# bike_light.net
KiCad netlist of a schematic drawn in EAGLE
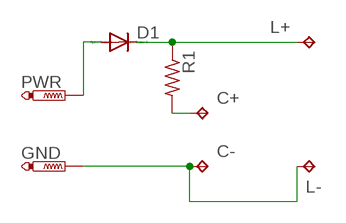
[diagram p0: schematic, sheet 1]

(export (version "E")
  (design (tool "Eeschema 10.0.6"))
  (components
    (comp (ref "C+")
      (value "TPTP20SQ")
      (footprint "eagle-import:TP20SQ")
      (libsource (lib "eagle-import") (part "TPTP20SQ"))
    )
    (comp (ref "C-")
      (value "TPTP20SQ")
      (footprint "eagle-import:TP20SQ")
      (libsource (lib "eagle-import") (part "TPTP20SQ"))
    )
    (comp (ref "D1")
      (value "DIODE-DO-214AC")
      (footprint "eagle-import:DO-214AC")
      (libsource (lib "eagle-import") (part "DIODE-DO-214AC"))
    )
    (comp (ref "GND")
      (value "PTR1PAD1-13Y")
      (footprint "eagle-import:P1-13Y")
      (libsource (lib "eagle-import") (part "PTR1PAD1-13Y"))
    )
    (comp (ref "L+")
      (value "TPTP20SQ")
      (footprint "eagle-import:TP20SQ")
      (libsource (lib "eagle-import") (part "TPTP20SQ"))
    )
    (comp (ref "L-")
      (value "TPTP20SQ")
      (footprint "eagle-import:TP20SQ")
      (libsource (lib "eagle-import") (part "TPTP20SQ"))
    )
    (comp (ref "PWR")
      (value "PTR1PAD1-13Y")
      (footprint "eagle-import:P1-13Y")
      (libsource (lib "eagle-import") (part "PTR1PAD1-13Y"))
    )
    (comp (ref "R1")
      (value "R-US_M1206")
      (footprint "eagle-import:M1206")
      (libsource (lib "eagle-import") (part "R-US_M1206"))
    )
  )
  (nets
    (net (code "1") (name "Net-(C+-PadTP)") (class "Default")
      (node (ref "C+") (pin "TP") (pinfunction "TP_TP") (pintype "input"))
      (node (ref "R1") (pin "2") (pinfunction "2_2") (pintype "passive"))
    )
    (net (code "2") (name "Net-(C--PadTP)") (class "Default")
      (node (ref "C-") (pin "TP") (pinfunction "TP_TP") (pintype "input"))
      (node (ref "GND") (pin "TP") (pinfunction "TP_TP") (pintype "input"))
      (node (ref "L-") (pin "TP") (pinfunction "TP_TP") (pintype "input"))
    )
    (net (code "3") (name "Net-(D1-PadA)") (class "Default")
      (node (ref "D1") (pin "A") (pinfunction "A_A") (pintype "passive"))
      (node (ref "PWR") (pin "TP") (pinfunction "TP_TP") (pintype "input"))
    )
    (net (code "4") (name "Net-(D1-PadC)") (class "Default")
      (node (ref "D1") (pin "C") (pinfunction "C_C") (pintype "passive"))
      (node (ref "L+") (pin "TP") (pinfunction "TP_TP") (pintype "input"))
      (node (ref "R1") (pin "1") (pinfunction "1_1") (pintype "passive"))
    )
  )
)
